# single-apa102c.net
KiCad netlist of a schematic drawn in EAGLE
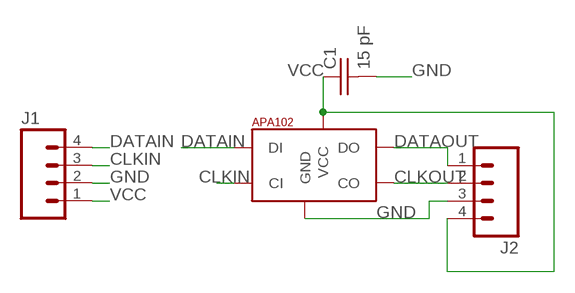
[diagram p0: schematic, sheet 1]
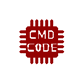
[diagram p1: schematic, sheet 2]

(export (version "E")
  (design (tool "Eeschema 10.0.6"))
  (components
    (comp (ref "U$2")
      (value "CMD_C0DE_LOGOCMD_CODE_LOGO_SILK")
      (footprint "eagle-import:CMD_C0DE_LOGO_SILK")
      (libsource (lib "eagle-import") (part "CMD_C0DE_LOGOCMD_CODE_LOGO_SILK"))
    )
    (comp (ref "C1")
      (value "15 pF")
      (footprint "eagle-import:C0805K")
      (libsource (lib "eagle-import") (part "C-USC0805K"))
    )
    (comp (ref "J1")
      (value "M04PTH")
      (footprint "eagle-import:1X04")
      (libsource (lib "eagle-import") (part "M04PTH"))
    )
    (comp (ref "J2")
      (value "M04PTH")
      (footprint "eagle-import:1X04")
      (libsource (lib "eagle-import") (part "M04PTH"))
    )
    (comp (ref "U$1")
      (value "APA1025050")
      (footprint "eagle-import:APA102_5050")
      (libsource (lib "eagle-import") (part "APA1025050"))
    )
  )
  (nets
    (net (code "1") (name "CLKIN") (class "Default")
      (node (ref "J1") (pin "3") (pinfunction "3_3") (pintype "passive"))
      (node (ref "U$1") (pin "5") (pinfunction "CI_5") (pintype "bidirectional"))
    )
    (net (code "2") (name "CLKOUT") (class "Default")
      (node (ref "J2") (pin "2") (pinfunction "2_2") (pintype "passive"))
      (node (ref "U$1") (pin "2") (pinfunction "CO_2") (pintype "bidirectional"))
    )
    (net (code "3") (name "DATAIN") (class "Default")
      (node (ref "J1") (pin "4") (pinfunction "4_4") (pintype "passive"))
      (node (ref "U$1") (pin "4") (pinfunction "DI_4") (pintype "bidirectional"))
    )
    (net (code "4") (name "DATAOUT") (class "Default")
      (node (ref "J2") (pin "1") (pinfunction "1_1") (pintype "passive"))
      (node (ref "U$1") (pin "3") (pinfunction "DO_3") (pintype "bidirectional"))
    )
    (net (code "5") (name "GND") (class "Default")
      (node (ref "C1") (pin "2") (pinfunction "2_2") (pintype "passive"))
      (node (ref "J1") (pin "2") (pinfunction "2_2") (pintype "passive"))
      (node (ref "J2") (pin "3") (pinfunction "3_3") (pintype "passive"))
      (node (ref "U$1") (pin "6") (pinfunction "GND_6") (pintype "bidirectional"))
    )
    (net (code "6") (name "VCC") (class "Default")
      (node (ref "C1") (pin "1") (pinfunction "1_1") (pintype "passive"))
      (node (ref "J1") (pin "1") (pinfunction "1_1") (pintype "passive"))
      (node (ref "J2") (pin "4") (pinfunction "4_4") (pintype "passive"))
      (node (ref "U$1") (pin "1") (pinfunction "VCC_1") (pintype "bidirectional"))
    )
  )
)
